# eagle1_schema.net
KiCad netlist of a schematic drawn in EAGLE
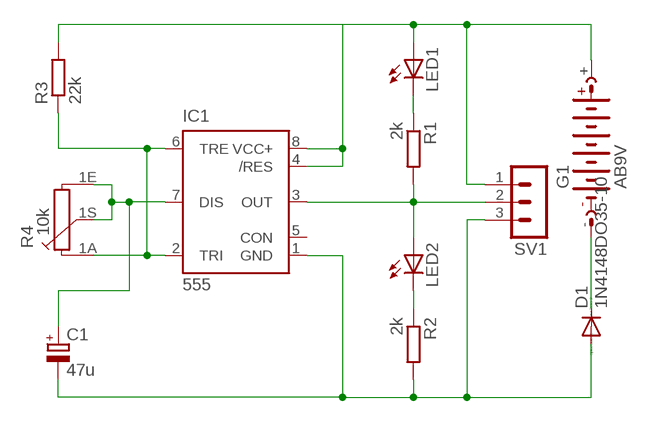
[diagram p0: schematic, sheet 1]

(export (version "E")
  (design (tool "Eeschema 10.0.6"))
  (components
    (comp (ref "C1")
      (value "47u")
      (footprint "eagle-import:E3,5-8")
      (libsource (lib "eagle-import") (part "CPOL-EUE3.5-8"))
    )
    (comp (ref "D1")
      (value "1N4148DO35-10")
      (footprint "eagle-import:DO35-10")
      (libsource (lib "eagle-import") (part "1N4148DO35-10"))
    )
    (comp (ref "G1")
      (value "AB9V")
      (footprint "eagle-import:AB9V")
      (libsource (lib "eagle-import") (part "AB9V"))
    )
    (comp (ref "IC1")
      (value "555")
      (footprint "eagle-import:DIP08")
      (libsource (lib "eagle-import") (part "555P"))
    )
    (comp (ref "LED1")
      (value "LED3MM")
      (footprint "eagle-import:LED3MM")
      (libsource (lib "eagle-import") (part "LED3MM"))
    )
    (comp (ref "LED2")
      (value "LED3MM")
      (footprint "eagle-import:LED3MM")
      (libsource (lib "eagle-import") (part "LED3MM"))
    )
    (comp (ref "R1")
      (value "2k")
      (footprint "eagle-import:0207_10")
      (libsource (lib "eagle-import") (part "R-EU_0207/10"))
    )
    (comp (ref "R2")
      (value "2k")
      (footprint "eagle-import:0207_10")
      (libsource (lib "eagle-import") (part "R-EU_0207/10"))
    )
    (comp (ref "R3")
      (value "22k")
      (footprint "eagle-import:0207_10")
      (libsource (lib "eagle-import") (part "R-EU_0207/10"))
    )
    (comp (ref "R4")
      (value "10k")
      (footprint "eagle-import:PC16S")
      (libsource (lib "eagle-import") (part "PC16S"))
    )
    (comp (ref "SV1")
      (value "MA03-1")
      (footprint "eagle-import:MA03-1")
      (libsource (lib "eagle-import") (part "MA03-1"))
    )
  )
  (nets
    (net (code "1") (name "Net-(D1-PadC)") (class "Default")
      (node (ref "D1") (pin "C") (pinfunction "C_C") (pintype "passive"))
      (node (ref "G1") (pin "-") (pinfunction "-_-") (pintype "passive"))
    )
    (net (code "2") (name "Net-(IC1-DIS)") (class "Default")
      (node (ref "C1") (pin "+") (pinfunction "+_+") (pintype "passive"))
      (node (ref "IC1") (pin "7") (pinfunction "DIS_7") (pintype "input"))
      (node (ref "R4") (pin "1E") (pinfunction "1E_1E") (pintype "passive"))
      (node (ref "R4") (pin "1S") (pinfunction "1S_1S") (pintype "passive"))
    )
    (net (code "3") (name "Net-(IC1-GND)") (class "Default")
      (node (ref "C1") (pin "-") (pinfunction "-_-") (pintype "passive"))
      (node (ref "D1") (pin "A") (pinfunction "A_A") (pintype "passive"))
      (node (ref "IC1") (pin "1") (pinfunction "GND_1") (pintype "power_in"))
      (node (ref "R2") (pin "2") (pinfunction "2_2") (pintype "passive"))
      (node (ref "SV1") (pin "3") (pinfunction "3_3") (pintype "passive"))
    )
    (net (code "4") (name "Net-(IC1-OUT)") (class "Default")
      (node (ref "IC1") (pin "3") (pinfunction "OUT_3") (pintype "output"))
      (node (ref "LED2") (pin "A") (pinfunction "A_A") (pintype "passive"))
      (node (ref "R1") (pin "2") (pinfunction "2_2") (pintype "passive"))
      (node (ref "SV1") (pin "2") (pinfunction "2_2") (pintype "passive"))
    )
    (net (code "5") (name "Net-(IC1-TRE)") (class "Default")
      (node (ref "IC1") (pin "2") (pinfunction "TRI_2") (pintype "input"))
      (node (ref "IC1") (pin "6") (pinfunction "TRE_6") (pintype "input"))
      (node (ref "R3") (pin "1") (pinfunction "1_1") (pintype "passive"))
      (node (ref "R4") (pin "1A") (pinfunction "1A_1A") (pintype "passive"))
    )
    (net (code "6") (name "Net-(IC1-VCC+)") (class "Default")
      (node (ref "G1") (pin "+") (pinfunction "+_+") (pintype "passive"))
      (node (ref "IC1") (pin "4") (pinfunction "/RES_4") (pintype "input"))
      (node (ref "IC1") (pin "8") (pinfunction "VCC+_8") (pintype "power_in"))
      (node (ref "LED1") (pin "A") (pinfunction "A_A") (pintype "passive"))
      (node (ref "R3") (pin "2") (pinfunction "2_2") (pintype "passive"))
      (node (ref "SV1") (pin "1") (pinfunction "1_1") (pintype "passive"))
    )
    (net (code "7") (name "Net-(LED1-C)") (class "Default")
      (node (ref "LED1") (pin "K") (pinfunction "C_K") (pintype "passive"))
      (node (ref "R1") (pin "1") (pinfunction "1_1") (pintype "passive"))
    )
    (net (code "8") (name "Net-(LED2-C)") (class "Default")
      (node (ref "LED2") (pin "K") (pinfunction "C_K") (pintype "passive"))
      (node (ref "R2") (pin "1") (pinfunction "1_1") (pintype "passive"))
    )
    (net (code "9") (name "unconnected-(IC1-CON-Pad5)") (class "Default")
      (node (ref "IC1") (pin "5") (pinfunction "CON_5") (pintype "input"))
    )
  )
)
